# Sheet1.net
KiCad netlist of a schematic drawn in Altium Designer
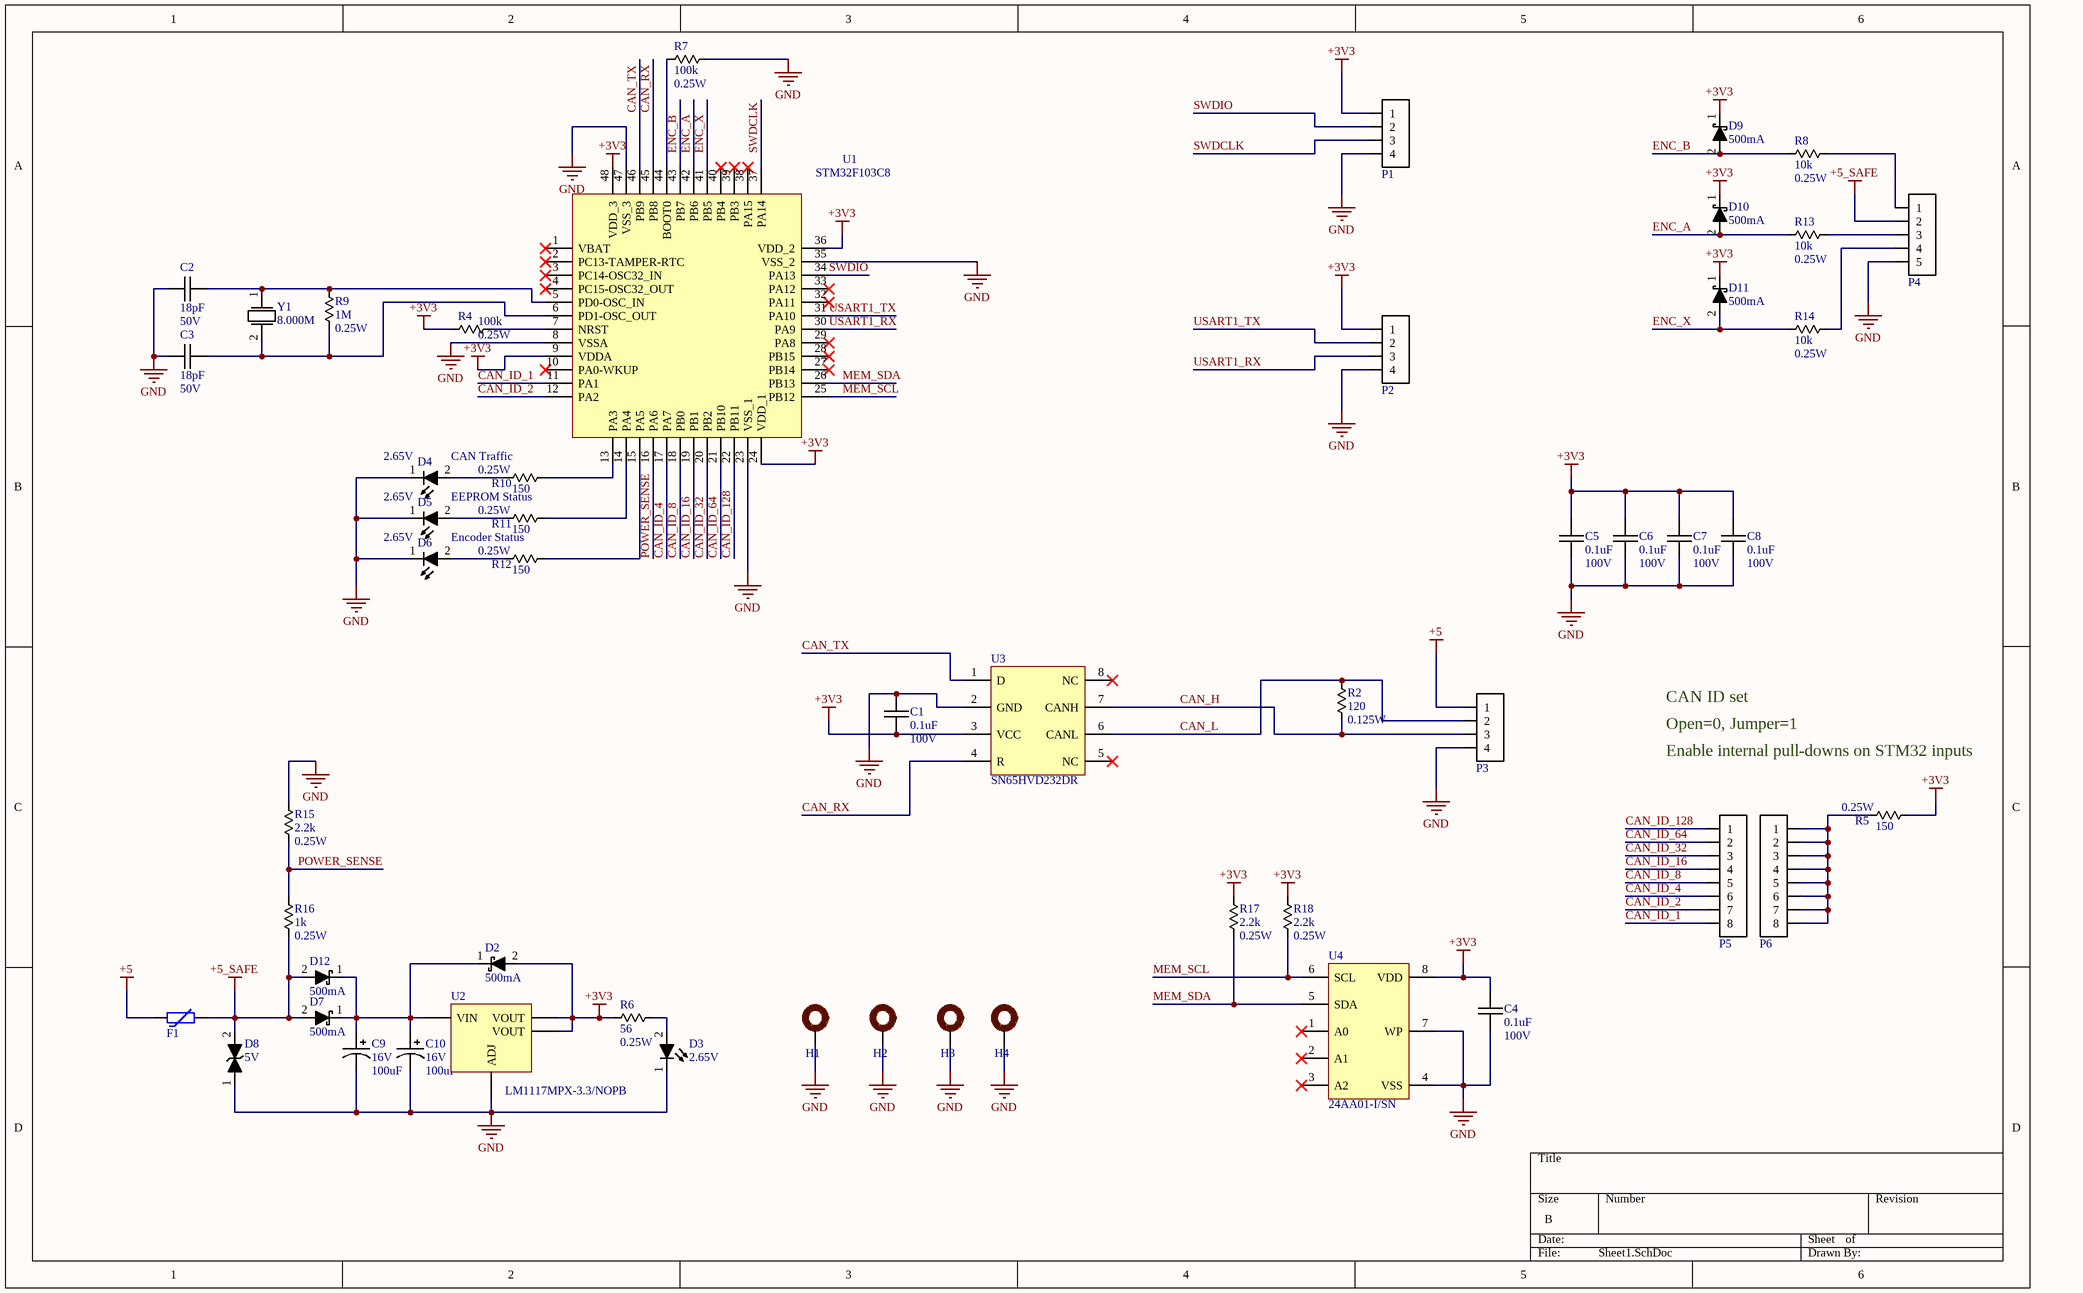
[diagram p0: Sheet1.SchDoc]

(export (version "E")
  (design (tool "Eeschema 10.0.6"))
  (components
    (comp (ref "C1")
      (value "cap_single_np")
      (footprint "chip_0603")
      (description "CAP, 0.1uF, ±10%, 100V, X7R, 0603")
      (fields
        (field (name "TOLERANCE") "±10%")
        (field (name "CAPACITANCE") "0.1uF")
        (field (name "VOLTAGE RATING") "100V")
        (field (name "PART NUMBER") "CAP-00477")
      )
      (libsource (lib "Capacitors") (part "cap_single_np"))
    )
    (comp (ref "C2")
      (value "cap_single_np")
      (footprint "chip_0603")
      (description "CAP, 18pF, ±2%, 50V, C0G, 0603")
      (fields
        (field (name "TOLERANCE") "±2%")
        (field (name "CAPACITANCE") "18pF")
        (field (name "VOLTAGE RATING") "50V")
        (field (name "PART NUMBER") "CAP-00409")
      )
      (libsource (lib "Capacitors") (part "cap_single_np"))
    )
    (comp (ref "C3")
      (value "cap_single_np")
      (footprint "chip_0603")
      (description "CAP, 18pF, ±2%, 50V, C0G, 0603")
      (fields
        (field (name "TOLERANCE") "±2%")
        (field (name "CAPACITANCE") "18pF")
        (field (name "VOLTAGE RATING") "50V")
        (field (name "PART NUMBER") "CAP-00409")
      )
      (libsource (lib "Capacitors") (part "cap_single_np"))
    )
    (comp (ref "C4")
      (value "cap_single_np")
      (footprint "chip_0603")
      (description "CAP, 0.1uF, ±10%, 100V, X7R, 0603")
      (fields
        (field (name "TOLERANCE") "±10%")
        (field (name "CAPACITANCE") "0.1uF")
        (field (name "VOLTAGE RATING") "100V")
        (field (name "PART NUMBER") "CAP-00477")
      )
      (libsource (lib "Capacitors") (part "cap_single_np"))
    )
    (comp (ref "C5")
      (value "cap_single_np")
      (footprint "chip_0603")
      (description "CAP, 0.1uF, ±10%, 100V, X7R, 0603")
      (fields
        (field (name "TOLERANCE") "±10%")
        (field (name "CAPACITANCE") "0.1uF")
        (field (name "VOLTAGE RATING") "100V")
        (field (name "PART NUMBER") "CAP-00530")
      )
      (libsource (lib "Capacitors") (part "cap_single_np"))
    )
    (comp (ref "C6")
      (value "cap_single_np")
      (footprint "chip_0603")
      (description "CAP, 0.1uF, ±10%, 100V, X7R, 0603")
      (fields
        (field (name "TOLERANCE") "±10%")
        (field (name "CAPACITANCE") "0.1uF")
        (field (name "VOLTAGE RATING") "100V")
        (field (name "PART NUMBER") "CAP-00530")
      )
      (libsource (lib "Capacitors") (part "cap_single_np"))
    )
    (comp (ref "C7")
      (value "cap_single_np")
      (footprint "chip_0603")
      (description "CAP, 0.1uF, ±10%, 100V, X7R, 0603")
      (fields
        (field (name "TOLERANCE") "±10%")
        (field (name "CAPACITANCE") "0.1uF")
        (field (name "VOLTAGE RATING") "100V")
        (field (name "PART NUMBER") "CAP-00530")
      )
      (libsource (lib "Capacitors") (part "cap_single_np"))
    )
    (comp (ref "C8")
      (value "cap_single_np")
      (footprint "chip_0603")
      (description "CAP, 0.1uF, ±10%, 100V, X7R, 0603")
      (fields
        (field (name "TOLERANCE") "±10%")
        (field (name "CAPACITANCE") "0.1uF")
        (field (name "VOLTAGE RATING") "100V")
        (field (name "PART NUMBER") "CAP-00530")
      )
      (libsource (lib "Capacitors") (part "cap_single_np"))
    )
    (comp (ref "C9")
      (value "cap_single_p")
      (footprint "chip_2917_AVX_TAJD")
      (description "CAP, 100uF, ±10%, 16V, Tantalum, 2917")
      (fields
        (field (name "TOLERANCE") "±10%")
        (field (name "VOLTAGE RATING") "16V")
        (field (name "CAPACITANCE") "100uF")
        (field (name "PART NUMBER") "CAP-00550")
      )
      (libsource (lib "Capacitors") (part "cap_single_p"))
    )
    (comp (ref "C10")
      (value "cap_single_p")
      (footprint "chip_2917_AVX_TAJD")
      (description "CAP, 100uF, ±10%, 16V, Tantalum, 2917")
      (fields
        (field (name "TOLERANCE") "±10%")
        (field (name "VOLTAGE RATING") "16V")
        (field (name "CAPACITANCE") "100uF")
        (field (name "PART NUMBER") "CAP-00550")
      )
      (libsource (lib "Capacitors") (part "cap_single_p"))
    )
    (comp (ref "D2")
      (value "diode_2")
      (footprint "sod323_0")
      (description "Dio Shtky, 500mA, 0.62V, 30V, SOD-323")
      (fields
        (field (name "CURRENT RATING") "500mA")
        (field (name "PART NUMBER") "DIO-00000")
        (field (name "MANUFACTURER") "ON Semi")
      )
      (libsource (lib "Diodes") (part "diode_2"))
    )
    (comp (ref "D3")
      (value "diode_4")
      (footprint "chip_0603")
      (description "LED, Green, 0603, Low current, HELI2 Series")
      (fields
        (field (name "FORWARD VOLTAGE") "2.65V")
        (field (name "PART NUMBER") "DIO-00050")
        (field (name "MANUFACTURER") "Kingbright")
      )
      (libsource (lib "Diodes") (part "diode_4"))
    )
    (comp (ref "D4")
      (value "diode_4")
      (footprint "chip_0603")
      (description "LED, Blue, 0603, Low current, HELI2 Series")
      (fields
        (field (name "FORWARD VOLTAGE") "2.65V")
        (field (name "PART NUMBER") "DIO-00049")
        (field (name "MANUFACTURER") "Kingbright")
      )
      (libsource (lib "Diodes") (part "diode_4"))
    )
    (comp (ref "D5")
      (value "diode_4")
      (footprint "chip_0603")
      (description "LED, Blue, 0603, Low current, HELI2 Series")
      (fields
        (field (name "FORWARD VOLTAGE") "2.65V")
        (field (name "PART NUMBER") "DIO-00049")
        (field (name "MANUFACTURER") "Kingbright")
      )
      (libsource (lib "Diodes") (part "diode_4"))
    )
    (comp (ref "D6")
      (value "diode_4")
      (footprint "chip_0603")
      (description "LED, Blue, 0603, Low current, HELI2 Series")
      (fields
        (field (name "FORWARD VOLTAGE") "2.65V")
        (field (name "PART NUMBER") "DIO-00049")
        (field (name "MANUFACTURER") "Kingbright")
      )
      (libsource (lib "Diodes") (part "diode_4"))
    )
    (comp (ref "D7")
      (value "diode_2")
      (footprint "sod323_0")
      (description "Dio Shtky, 500mA, 0.62V, 30V, SOD-323")
      (fields
        (field (name "CURRENT RATING") "500mA")
        (field (name "PART NUMBER") "DIO-00000")
        (field (name "MANUFACTURER") "ON Semi")
      )
      (libsource (lib "Diodes") (part "diode_2"))
    )
    (comp (ref "D8")
      (value "diode_5")
      (footprint "sod323_0")
      (description "TVS, 5V, 500W")
      (fields
        (field (name "REVERSE BREAKDOWN VOLTAGE") "5V")
        (field (name "PART NUMBER") "DIO-00037")
        (field (name "MANUFACTURER") "ST")
      )
      (libsource (lib "Diodes") (part "diode_5"))
    )
    (comp (ref "D9")
      (value "diode_2")
      (footprint "sod323_0")
      (description "Dio Shtky, 500mA, 0.62V, 30V, SOD-323")
      (fields
        (field (name "CURRENT RATING") "500mA")
        (field (name "PART NUMBER") "DIO-00000")
        (field (name "MANUFACTURER") "ON Semi")
      )
      (libsource (lib "Diodes") (part "diode_2"))
    )
    (comp (ref "D10")
      (value "diode_2")
      (footprint "sod323_0")
      (description "Dio Shtky, 500mA, 0.62V, 30V, SOD-323")
      (fields
        (field (name "CURRENT RATING") "500mA")
        (field (name "PART NUMBER") "DIO-00000")
        (field (name "MANUFACTURER") "ON Semi")
      )
      (libsource (lib "Diodes") (part "diode_2"))
    )
    (comp (ref "D11")
      (value "diode_2")
      (footprint "sod323_0")
      (description "Dio Shtky, 500mA, 0.62V, 30V, SOD-323")
      (fields
        (field (name "CURRENT RATING") "500mA")
        (field (name "PART NUMBER") "DIO-00000")
        (field (name "MANUFACTURER") "ON Semi")
      )
      (libsource (lib "Diodes") (part "diode_2"))
    )
    (comp (ref "D12")
      (value "diode_2")
      (footprint "sod323_0")
      (description "Dio Shtky, 500mA, 0.62V, 30V, SOD-323")
      (fields
        (field (name "CURRENT RATING") "500mA")
        (field (name "PART NUMBER") "DIO-00000")
        (field (name "MANUFACTURER") "ON Semi")
      )
      (libsource (lib "Diodes") (part "diode_2"))
    )
    (comp (ref "F1")
      (value "PTC_0")
      (footprint "chip_1206")
      (description "PTC Resettable fuse, 6V, 500mA, 1206")
      (fields (field (name "PART NUMBER") "MISC-00008") (field (name "MANUFACTURER") "Eaton"))
      (libsource (lib "Misc") (part "PTC_0"))
    )
    (comp (ref "H1")
      (value "mounting_hole_0")
      (footprint "#8-32_SOCKET_HEAD")
      (description "#8-32 Mounting Hole for Socket Head Cap Screw")
      (fields (field (name "PART NUMBER") "MISC-00027"))
      (libsource (lib "Misc") (part "mounting_hole_0"))
    )
    (comp (ref "H2")
      (value "mounting_hole_0")
      (footprint "#8-32_SOCKET_HEAD")
      (description "#8-32 Mounting Hole for Socket Head Cap Screw")
      (fields (field (name "PART NUMBER") "MISC-00027"))
      (libsource (lib "Misc") (part "mounting_hole_0"))
    )
    (comp (ref "H3")
      (value "mounting_hole_0")
      (footprint "#8-32_SOCKET_HEAD")
      (description "#8-32 Mounting Hole for Socket Head Cap Screw")
      (fields (field (name "PART NUMBER") "MISC-00027"))
      (libsource (lib "Misc") (part "mounting_hole_0"))
    )
    (comp (ref "H4")
      (value "mounting_hole_0")
      (footprint "#8-32_SOCKET_HEAD")
      (description "#8-32 Mounting Hole for Socket Head Cap Screw")
      (fields (field (name "PART NUMBER") "MISC-00027"))
      (libsource (lib "Misc") (part "mounting_hole_0"))
    )
    (comp (ref "P1")
      (value "conn-4x1_0")
      (footprint "HDDR_4x1_0")
      (description "Header 4x1, 0.1\"")
      (fields (field (name "PART NUMBER") "CONN-00029"))
      (libsource (lib "Connectors") (part "conn-4x1_0"))
    )
    (comp (ref "P2")
      (value "conn-4x1_0")
      (footprint "HDDR_4x1_0")
      (description "Header 4x1, 0.1\"")
      (fields (field (name "PART NUMBER") "CONN-00029"))
      (libsource (lib "Connectors") (part "conn-4x1_0"))
    )
    (comp (ref "P3")
      (value "conn-4x1_0")
      (footprint "TERM_3.50MM_4x1_0")
      (description "Term Blk, 4 Pos, 16A, 3.5mm Pitch")
      (fields (field (name "PART NUMBER") "CONN-00024") (field (name "MANUFACTURER") "Phoenix Contact"))
      (libsource (lib "Connectors") (part "conn-4x1_0"))
    )
    (comp (ref "P4")
      (value "conn-5x1_0")
      (footprint "JST_PHR_5_0")
      (description "JST PHR 5x1")
      (fields (field (name "PART NUMBER") "CONN-00016") (field (name "MANUFACTURER") "JST"))
      (libsource (lib "Connectors") (part "conn-5x1_0"))
    )
    (comp (ref "P5")
      (value "conn-8x1_0")
      (footprint "hddr_8x1_0")
      (description "Header 8x1, 0.1\"")
      (fields (field (name "PART NUMBER") "CONN-00003"))
      (libsource (lib "Connectors") (part "conn-8x1_0"))
    )
    (comp (ref "P6")
      (value "conn-8x1_0")
      (footprint "hddr_8x1_0")
      (description "Header 8x1, 0.1\"")
      (fields (field (name "PART NUMBER") "CONN-00003"))
      (libsource (lib "Connectors") (part "conn-8x1_0"))
    )
    (comp (ref "R2")
      (value "res_single")
      (footprint "chip_0805")
      (description "RES SMD 120 OHM 1% 1/8W 0805")
      (fields
        (field (name "TOLERANCE") "1%")
        (field (name "RESISTANCE") "120")
        (field (name "POWER RATING") "0.125W")
        (field (name "PART NUMBER") "RES-00183")
      )
      (libsource (lib "Resistors") (part "res_single"))
    )
    (comp (ref "R4")
      (value "res_single")
      (footprint "chip_0603")
      (description "RES SMD 100K OHM 1% 1/4W 0603")
      (fields
        (field (name "TOLERANCE") "1%")
        (field (name "RESISTANCE") "100k")
        (field (name "POWER RATING") "0.25W")
        (field (name "PART NUMBER") "RES-00301")
      )
      (libsource (lib "Resistors") (part "res_single"))
    )
    (comp (ref "R5")
      (value "res_single")
      (footprint "chip_0603")
      (description "RES SMD 150 OHM 1% 1/4W 0603")
      (fields
        (field (name "TOLERANCE") "1%")
        (field (name "RESISTANCE") "150")
        (field (name "POWER RATING") "0.25W")
        (field (name "PART NUMBER") "RES-00188")
      )
      (libsource (lib "Resistors") (part "res_single"))
    )
    (comp (ref "R6")
      (value "res_single")
      (footprint "chip_0603")
      (description "RES SMD 56 OHM 1% 1/4W 0603")
      (fields
        (field (name "TOLERANCE") "1%")
        (field (name "RESISTANCE") "56")
        (field (name "POWER RATING") "0.25W")
        (field (name "PART NUMBER") "RES-00159")
      )
      (libsource (lib "Resistors") (part "res_single"))
    )
    (comp (ref "R7")
      (value "res_single")
      (footprint "chip_0603")
      (description "RES SMD 100K OHM 1% 1/4W 0603")
      (fields
        (field (name "TOLERANCE") "1%")
        (field (name "RESISTANCE") "100k")
        (field (name "POWER RATING") "0.25W")
        (field (name "PART NUMBER") "RES-00301")
      )
      (libsource (lib "Resistors") (part "res_single"))
    )
    (comp (ref "R8")
      (value "res_single")
      (footprint "chip_0603")
      (description "RES SMD 10K OHM 1% 1/4W 0603")
      (fields
        (field (name "TOLERANCE") "1%")
        (field (name "RESISTANCE") "10k")
        (field (name "POWER RATING") "0.25W")
        (field (name "PART NUMBER") "RES-00306")
      )
      (libsource (lib "Resistors") (part "res_single"))
    )
    (comp (ref "R9")
      (value "res_single")
      (footprint "chip_0603")
      (description "RES SMD 1M OHM 1% 1/4W 0603")
      (fields
        (field (name "TOLERANCE") "1%")
        (field (name "RESISTANCE") "1M")
        (field (name "POWER RATING") "0.25W")
        (field (name "PART NUMBER") "RES-00362")
      )
      (libsource (lib "Resistors") (part "res_single"))
    )
    (comp (ref "R10")
      (value "res_single")
      (footprint "chip_0603")
      (description "RES SMD 150 OHM 1% 1/4W 0603")
      (fields
        (field (name "TOLERANCE") "1%")
        (field (name "RESISTANCE") "150")
        (field (name "POWER RATING") "0.25W")
        (field (name "PART NUMBER") "RES-00188")
      )
      (libsource (lib "Resistors") (part "res_single"))
    )
    (comp (ref "R11")
      (value "res_single")
      (footprint "chip_0603")
      (description "RES SMD 150 OHM 1% 1/4W 0603")
      (fields
        (field (name "TOLERANCE") "1%")
        (field (name "RESISTANCE") "150")
        (field (name "POWER RATING") "0.25W")
        (field (name "PART NUMBER") "RES-00188")
      )
      (libsource (lib "Resistors") (part "res_single"))
    )
    (comp (ref "R12")
      (value "res_single")
      (footprint "chip_0603")
      (description "RES SMD 150 OHM 1% 1/4W 0603")
      (fields
        (field (name "TOLERANCE") "1%")
        (field (name "RESISTANCE") "150")
        (field (name "POWER RATING") "0.25W")
        (field (name "PART NUMBER") "RES-00188")
      )
      (libsource (lib "Resistors") (part "res_single"))
    )
    (comp (ref "R13")
      (value "res_single")
      (footprint "chip_0603")
      (description "RES SMD 10K OHM 1% 1/4W 0603")
      (fields
        (field (name "TOLERANCE") "1%")
        (field (name "RESISTANCE") "10k")
        (field (name "POWER RATING") "0.25W")
        (field (name "PART NUMBER") "RES-00306")
      )
      (libsource (lib "Resistors") (part "res_single"))
    )
    (comp (ref "R14")
      (value "res_single")
      (footprint "chip_0603")
      (description "RES SMD 10K OHM 1% 1/4W 0603")
      (fields
        (field (name "TOLERANCE") "1%")
        (field (name "RESISTANCE") "10k")
        (field (name "POWER RATING") "0.25W")
        (field (name "PART NUMBER") "RES-00306")
      )
      (libsource (lib "Resistors") (part "res_single"))
    )
    (comp (ref "R15")
      (value "res_single")
      (footprint "chip_0603")
      (description "RES SMD 2.2K OHM 1% 1/4W 0603")
      (fields
        (field (name "TOLERANCE") "1%")
        (field (name "RESISTANCE") "2.2k")
        (field (name "POWER RATING") "0.25W")
        (field (name "PART NUMBER") "RES-00365")
      )
      (libsource (lib "Resistors") (part "res_single"))
    )
    (comp (ref "R16")
      (value "res_single")
      (footprint "chip_0603")
      (description "RES SMD 1K OHM 1% 1/4W 0603")
      (fields
        (field (name "TOLERANCE") "1%")
        (field (name "RESISTANCE") "1k")
        (field (name "POWER RATING") "0.25W")
        (field (name "PART NUMBER") "RES-00360")
      )
      (libsource (lib "Resistors") (part "res_single"))
    )
    (comp (ref "R17")
      (value "res_single")
      (footprint "chip_0603")
      (description "RES SMD 2.2K OHM 1% 1/4W 0603")
      (fields
        (field (name "TOLERANCE") "1%")
        (field (name "RESISTANCE") "2.2k")
        (field (name "POWER RATING") "0.25W")
        (field (name "PART NUMBER") "RES-00365")
      )
      (libsource (lib "Resistors") (part "res_single"))
    )
    (comp (ref "R18")
      (value "res_single")
      (footprint "chip_0603")
      (description "RES SMD 2.2K OHM 1% 1/4W 0603")
      (fields
        (field (name "TOLERANCE") "1%")
        (field (name "RESISTANCE") "2.2k")
        (field (name "POWER RATING") "0.25W")
        (field (name "PART NUMBER") "RES-00365")
      )
      (libsource (lib "Resistors") (part "res_single"))
    )
    (comp (ref "U1")
      (value "STM32F103C8")
      (footprint "LQFP48_0")
      (description "STM32 M3, LQFP-48")
      (fields
        (field (name "MANUFACTURER PN") "STM32F103C8")
        (field (name "PART NUMBER") "UCTRL-00008")
        (field (name "MANUFACTURER") "ST")
      )
      (libsource (lib "Microcontrollers") (part "STM32F103C8"))
    )
    (comp (ref "U2")
      (value "LM1117")
      (footprint "sot-223-4")
      (description "REG, Linear, Fixed 3V3, 800mA, SOT-223")
      (fields
        (field (name "MANUFACTURER PN") "LM1117MPX-3.3/NOPB")
        (field (name "PART NUMBER") "PWREG-00018")
        (field (name "MANUFACTURER") "TI")
      )
      (libsource (lib "Power Reg") (part "LM1117"))
    )
    (comp (ref "U3")
      (value "SN65HVD232")
      (footprint "SO-8")
      (description "CANbus Transceiver, Single channel, SN65HVD232")
      (fields
        (field (name "MANUFACTURER PN") "SN65HVD232DR")
        (field (name "PART NUMBER") "IFACE-00008")
        (field (name "MANUFACTURER") "TI")
      )
      (libsource (lib "Interfaces") (part "SN65HVD232"))
    )
    (comp (ref "U4")
      (value "24AA01")
      (footprint "SO-8")
      (description "EEPROM, 1K-bit, I2C, 400kHz, 24AA01, 8-SOIC")
      (fields
        (field (name "MANUFACTURER PN") "24AA01-I/SN")
        (field (name "PART NUMBER") "LOGIC-00028")
        (field (name "MANUFACTURER") "Microchip")
      )
      (libsource (lib "Logic") (part "24AA01"))
    )
    (comp (ref "Y1")
      (value "osc_xtal_2p_0")
      (footprint "ABLS_AT49_OSC")
      (description "XTAL, 8MHz, 18pF, 20ppm")
      (fields
        (field (name "TOLERANCE") "20ppm")
        (field (name "FREQUENCY") "8.000M")
        (field (name "PART NUMBER") "OSC-00002")
      )
      (libsource (lib "Oscillators") (part "osc_xtal_2p_0"))
    )
  )
  (nets
    (net (code "1") (name "+3V3") (class "Default")
      (node (ref "C1") (pin "2") (pinfunction "2_2") (pintype "passive"))
      (node (ref "C4") (pin "1") (pinfunction "1_1") (pintype "passive"))
      (node (ref "C5") (pin "2") (pinfunction "2_2") (pintype "passive"))
      (node (ref "C6") (pin "2") (pinfunction "2_2") (pintype "passive"))
      (node (ref "C7") (pin "2") (pinfunction "2_2") (pintype "passive"))
      (node (ref "C8") (pin "2") (pinfunction "2_2") (pintype "passive"))
      (node (ref "D10") (pin "1") (pinfunction "1_1") (pintype "passive"))
      (node (ref "D11") (pin "1") (pinfunction "1_1") (pintype "passive"))
      (node (ref "D2") (pin "2") (pinfunction "2_2") (pintype "passive"))
      (node (ref "D9") (pin "1") (pinfunction "1_1") (pintype "passive"))
      (node (ref "P1") (pin "1") (pinfunction "1_1") (pintype "passive"))
      (node (ref "P2") (pin "1") (pinfunction "1_1") (pintype "passive"))
      (node (ref "R17") (pin "1") (pinfunction "1_1") (pintype "passive"))
      (node (ref "R18") (pin "1") (pinfunction "1_1") (pintype "passive"))
      (node (ref "R4") (pin "2") (pinfunction "2_2") (pintype "passive"))
      (node (ref "R5") (pin "2") (pinfunction "2_2") (pintype "passive"))
      (node (ref "R6") (pin "1") (pinfunction "1_1") (pintype "passive"))
      (node (ref "U1") (pin "24") (pinfunction "VDD_1_24") (pintype "passive"))
      (node (ref "U1") (pin "36") (pinfunction "VDD_2_36") (pintype "passive"))
      (node (ref "U1") (pin "48") (pinfunction "VDD_3_48") (pintype "passive"))
      (node (ref "U1") (pin "9") (pinfunction "VDDA_9") (pintype "passive"))
      (node (ref "U2") (pin "2") (pinfunction "VOUT_2") (pintype "passive"))
      (node (ref "U2") (pin "4") (pinfunction "VOUT_4") (pintype "passive"))
      (node (ref "U3") (pin "3") (pinfunction "VCC_3") (pintype "passive"))
      (node (ref "U4") (pin "8") (pinfunction "VDD_8") (pintype "passive"))
    )
    (net (code "2") (name "+5") (class "Default")
      (node (ref "F1") (pin "1") (pinfunction "1_1") (pintype "passive"))
      (node (ref "P3") (pin "1") (pinfunction "1_1") (pintype "passive"))
    )
    (net (code "3") (name "+5_SAFE") (class "Default")
      (node (ref "D12") (pin "2") (pinfunction "2_2") (pintype "passive"))
      (node (ref "D7") (pin "2") (pinfunction "2_2") (pintype "passive"))
      (node (ref "D8") (pin "2") (pinfunction "2_2") (pintype "passive"))
      (node (ref "F1") (pin "2") (pinfunction "2_2") (pintype "passive"))
      (node (ref "P4") (pin "2") (pinfunction "2_2") (pintype "passive"))
      (node (ref "R16") (pin "2") (pinfunction "2_2") (pintype "passive"))
    )
    (net (code "4") (name "/CAN_H") (class "Default")
      (node (ref "P3") (pin "3") (pinfunction "3_3") (pintype "passive"))
      (node (ref "R2") (pin "2") (pinfunction "2_2") (pintype "passive"))
      (node (ref "U3") (pin "7") (pinfunction "CANH_7") (pintype "passive"))
    )
    (net (code "5") (name "/CAN_ID_1") (class "Default")
      (node (ref "P5") (pin "8") (pinfunction "8_8") (pintype "passive"))
      (node (ref "U1") (pin "11") (pinfunction "PA1_11") (pintype "passive"))
    )
    (net (code "6") (name "/CAN_ID_2") (class "Default")
      (node (ref "P5") (pin "7") (pinfunction "7_7") (pintype "passive"))
      (node (ref "U1") (pin "12") (pinfunction "PA2_12") (pintype "passive"))
    )
    (net (code "7") (name "/CAN_ID_4") (class "Default")
      (node (ref "P5") (pin "6") (pinfunction "6_6") (pintype "passive"))
      (node (ref "U1") (pin "17") (pinfunction "PA7_17") (pintype "passive"))
    )
    (net (code "8") (name "/CAN_ID_8") (class "Default")
      (node (ref "P5") (pin "5") (pinfunction "5_5") (pintype "passive"))
      (node (ref "U1") (pin "18") (pinfunction "PB0_18") (pintype "passive"))
    )
    (net (code "9") (name "/CAN_ID_16") (class "Default")
      (node (ref "P5") (pin "4") (pinfunction "4_4") (pintype "passive"))
      (node (ref "U1") (pin "19") (pinfunction "PB1_19") (pintype "passive"))
    )
    (net (code "10") (name "/CAN_ID_32") (class "Default")
      (node (ref "P5") (pin "3") (pinfunction "3_3") (pintype "passive"))
      (node (ref "U1") (pin "20") (pinfunction "PB2_20") (pintype "passive"))
    )
    (net (code "11") (name "/CAN_ID_64") (class "Default")
      (node (ref "P5") (pin "2") (pinfunction "2_2") (pintype "passive"))
      (node (ref "U1") (pin "21") (pinfunction "PB10_21") (pintype "passive"))
    )
    (net (code "12") (name "/CAN_ID_128") (class "Default")
      (node (ref "P5") (pin "1") (pinfunction "1_1") (pintype "passive"))
      (node (ref "U1") (pin "22") (pinfunction "PB11_22") (pintype "passive"))
    )
    (net (code "13") (name "/CAN_L") (class "Default")
      (node (ref "P3") (pin "2") (pinfunction "2_2") (pintype "passive"))
      (node (ref "R2") (pin "1") (pinfunction "1_1") (pintype "passive"))
      (node (ref "U3") (pin "6") (pinfunction "CANL_6") (pintype "passive"))
    )
    (net (code "14") (name "/CAN_RX") (class "Default")
      (node (ref "U1") (pin "45") (pinfunction "PB8_45") (pintype "passive"))
      (node (ref "U3") (pin "4") (pinfunction "R_4") (pintype "passive"))
    )
    (net (code "15") (name "/CAN_TX") (class "Default")
      (node (ref "U1") (pin "46") (pinfunction "PB9_46") (pintype "passive"))
      (node (ref "U3") (pin "1") (pinfunction "D_1") (pintype "passive"))
    )
    (net (code "16") (name "/ENC_A") (class "Default")
      (node (ref "D10") (pin "2") (pinfunction "2_2") (pintype "passive"))
      (node (ref "R13") (pin "1") (pinfunction "1_1") (pintype "passive"))
      (node (ref "U1") (pin "42") (pinfunction "PB6_42") (pintype "passive"))
    )
    (net (code "17") (name "/ENC_B") (class "Default")
      (node (ref "D9") (pin "2") (pinfunction "2_2") (pintype "passive"))
      (node (ref "R8") (pin "1") (pinfunction "1_1") (pintype "passive"))
      (node (ref "U1") (pin "43") (pinfunction "PB7_43") (pintype "passive"))
    )
    (net (code "18") (name "/ENC_X") (class "Default")
      (node (ref "D11") (pin "2") (pinfunction "2_2") (pintype "passive"))
      (node (ref "R14") (pin "1") (pinfunction "1_1") (pintype "passive"))
      (node (ref "U1") (pin "41") (pinfunction "PB5_41") (pintype "passive"))
    )
    (net (code "19") (name "/MEM_SCL") (class "Default")
      (node (ref "R18") (pin "2") (pinfunction "2_2") (pintype "passive"))
      (node (ref "U1") (pin "25") (pinfunction "PB12_25") (pintype "passive"))
      (node (ref "U4") (pin "6") (pinfunction "SCL_6") (pintype "passive"))
    )
    (net (code "20") (name "/MEM_SDA") (class "Default")
      (node (ref "R17") (pin "2") (pinfunction "2_2") (pintype "passive"))
      (node (ref "U1") (pin "26") (pinfunction "PB13_26") (pintype "passive"))
      (node (ref "U4") (pin "5") (pinfunction "SDA_5") (pintype "passive"))
    )
    (net (code "21") (name "/POWER_SENSE") (class "Default")
      (node (ref "R15") (pin "2") (pinfunction "2_2") (pintype "passive"))
      (node (ref "R16") (pin "1") (pinfunction "1_1") (pintype "passive"))
      (node (ref "U1") (pin "16") (pinfunction "PA6_16") (pintype "passive"))
    )
    (net (code "22") (name "/SWDCLK") (class "Default")
      (node (ref "P1") (pin "3") (pinfunction "3_3") (pintype "passive"))
      (node (ref "U1") (pin "37") (pinfunction "PA14_37") (pintype "passive"))
    )
    (net (code "23") (name "/SWDIO") (class "Default")
      (node (ref "P1") (pin "2") (pinfunction "2_2") (pintype "passive"))
      (node (ref "U1") (pin "34") (pinfunction "PA13_34") (pintype "passive"))
    )
    (net (code "24") (name "/USART1_RX") (class "Default")
      (node (ref "P2") (pin "3") (pinfunction "3_3") (pintype "passive"))
      (node (ref "U1") (pin "30") (pinfunction "PA9_30") (pintype "passive"))
    )
    (net (code "25") (name "/USART1_TX") (class "Default")
      (node (ref "P2") (pin "2") (pinfunction "2_2") (pintype "passive"))
      (node (ref "U1") (pin "31") (pinfunction "PA10_31") (pintype "passive"))
    )
    (net (code "26") (name "GND") (class "Default")
      (node (ref "C1") (pin "1") (pinfunction "1_1") (pintype "passive"))
      (node (ref "C10") (pin "2") (pinfunction "2_2") (pintype "passive"))
      (node (ref "C2") (pin "2") (pinfunction "2_2") (pintype "passive"))
      (node (ref "C3") (pin "2") (pinfunction "2_2") (pintype "passive"))
      (node (ref "C4") (pin "2") (pinfunction "2_2") (pintype "passive"))
      (node (ref "C5") (pin "1") (pinfunction "1_1") (pintype "passive"))
      (node (ref "C6") (pin "1") (pinfunction "1_1") (pintype "passive"))
      (node (ref "C7") (pin "1") (pinfunction "1_1") (pintype "passive"))
      (node (ref "C8") (pin "1") (pinfunction "1_1") (pintype "passive"))
      (node (ref "C9") (pin "2") (pinfunction "2_2") (pintype "passive"))
      (node (ref "D3") (pin "1") (pinfunction "1_1") (pintype "passive"))
      (node (ref "D4") (pin "1") (pinfunction "1_1") (pintype "passive"))
      (node (ref "D5") (pin "1") (pinfunction "1_1") (pintype "passive"))
      (node (ref "D6") (pin "1") (pinfunction "1_1") (pintype "passive"))
      (node (ref "D8") (pin "1") (pinfunction "1_1") (pintype "passive"))
      (node (ref "H1") (pin "0") (pinfunction "A_0") (pintype "passive"))
      (node (ref "H2") (pin "0") (pinfunction "A_0") (pintype "passive"))
      (node (ref "H3") (pin "0") (pinfunction "A_0") (pintype "passive"))
      (node (ref "H4") (pin "0") (pinfunction "A_0") (pintype "passive"))
      (node (ref "P1") (pin "4") (pinfunction "4_4") (pintype "passive"))
      (node (ref "P2") (pin "4") (pinfunction "4_4") (pintype "passive"))
      (node (ref "P3") (pin "4") (pinfunction "4_4") (pintype "passive"))
      (node (ref "P4") (pin "5") (pinfunction "5_5") (pintype "passive"))
      (node (ref "R15") (pin "1") (pinfunction "1_1") (pintype "passive"))
      (node (ref "R7") (pin "1") (pinfunction "1_1") (pintype "passive"))
      (node (ref "U1") (pin "23") (pinfunction "VSS_1_23") (pintype "passive"))
      (node (ref "U1") (pin "35") (pinfunction "VSS_2_35") (pintype "passive"))
      (node (ref "U1") (pin "47") (pinfunction "VSS_3_47") (pintype "passive"))
      (node (ref "U1") (pin "8") (pinfunction "VSSA_8") (pintype "passive"))
      (node (ref "U2") (pin "1") (pinfunction "ADJ_1") (pintype "passive"))
      (node (ref "U3") (pin "2") (pinfunction "GND_2") (pintype "passive"))
      (node (ref "U4") (pin "4") (pinfunction "VSS_4") (pintype "passive"))
      (node (ref "U4") (pin "7") (pinfunction "WP_7") (pintype "passive"))
    )
    (net (code "27") (name "Net-(D3-Pad2)") (class "Default")
      (node (ref "D3") (pin "2") (pinfunction "2_2") (pintype "passive"))
      (node (ref "R6") (pin "2") (pinfunction "2_2") (pintype "passive"))
    )
    (net (code "28") (name "Net-(D4-Pad2)") (class "Default")
      (node (ref "D4") (pin "2") (pinfunction "2_2") (pintype "passive"))
      (node (ref "R10") (pin "1") (pinfunction "1_1") (pintype "passive"))
    )
    (net (code "29") (name "Net-(D5-Pad2)") (class "Default")
      (node (ref "D5") (pin "2") (pinfunction "2_2") (pintype "passive"))
      (node (ref "R11") (pin "1") (pinfunction "1_1") (pintype "passive"))
    )
    (net (code "30") (name "Net-(D6-Pad2)") (class "Default")
      (node (ref "D6") (pin "2") (pinfunction "2_2") (pintype "passive"))
      (node (ref "R12") (pin "1") (pinfunction "1_1") (pintype "passive"))
    )
    (net (code "31") (name "Net-(P4-Pad1)") (class "Default")
      (node (ref "P4") (pin "1") (pinfunction "1_1") (pintype "passive"))
      (node (ref "R8") (pin "2") (pinfunction "2_2") (pintype "passive"))
    )
    (net (code "32") (name "Net-(P4-Pad3)") (class "Default")
      (node (ref "P4") (pin "3") (pinfunction "3_3") (pintype "passive"))
      (node (ref "R13") (pin "2") (pinfunction "2_2") (pintype "passive"))
    )
    (net (code "33") (name "Net-(P4-Pad4)") (class "Default")
      (node (ref "P4") (pin "4") (pinfunction "4_4") (pintype "passive"))
      (node (ref "R14") (pin "2") (pinfunction "2_2") (pintype "passive"))
    )
    (net (code "34") (name "Net-(P6-Pad1)") (class "Default")
      (node (ref "P6") (pin "1") (pinfunction "1_1") (pintype "passive"))
      (node (ref "P6") (pin "2") (pinfunction "2_2") (pintype "passive"))
      (node (ref "P6") (pin "3") (pinfunction "3_3") (pintype "passive"))
      (node (ref "P6") (pin "4") (pinfunction "4_4") (pintype "passive"))
      (node (ref "P6") (pin "5") (pinfunction "5_5") (pintype "passive"))
      (node (ref "P6") (pin "6") (pinfunction "6_6") (pintype "passive"))
      (node (ref "P6") (pin "7") (pinfunction "7_7") (pintype "passive"))
      (node (ref "P6") (pin "8") (pinfunction "8_8") (pintype "passive"))
      (node (ref "R5") (pin "1") (pinfunction "1_1") (pintype "passive"))
    )
    (net (code "35") (name "Net-(U1-BOOT0)") (class "Default")
      (node (ref "R7") (pin "2") (pinfunction "2_2") (pintype "passive"))
      (node (ref "U1") (pin "44") (pinfunction "BOOT0_44") (pintype "passive"))
    )
    (net (code "36") (name "Net-(U1-NRST)") (class "Default")
      (node (ref "R4") (pin "1") (pinfunction "1_1") (pintype "passive"))
      (node (ref "U1") (pin "7") (pinfunction "NRST_7") (pintype "passive"))
    )
    (net (code "37") (name "Net-(U1-PA3)") (class "Default")
      (node (ref "R10") (pin "2") (pinfunction "2_2") (pintype "passive"))
      (node (ref "U1") (pin "13") (pinfunction "PA3_13") (pintype "passive"))
    )
    (net (code "38") (name "Net-(U1-PA4)") (class "Default")
      (node (ref "R11") (pin "2") (pinfunction "2_2") (pintype "passive"))
      (node (ref "U1") (pin "14") (pinfunction "PA4_14") (pintype "passive"))
    )
    (net (code "39") (name "Net-(U1-PA5)") (class "Default")
      (node (ref "R12") (pin "2") (pinfunction "2_2") (pintype "passive"))
      (node (ref "U1") (pin "15") (pinfunction "PA5_15") (pintype "passive"))
    )
    (net (code "40") (name "Net-(U1-PD0-OSC_IN)") (class "Default")
      (node (ref "C2") (pin "1") (pinfunction "1_1") (pintype "passive"))
      (node (ref "R9") (pin "1") (pinfunction "1_1") (pintype "passive"))
      (node (ref "U1") (pin "5") (pinfunction "PD0-OSC_IN_5") (pintype "passive"))
      (node (ref "Y1") (pin "1") (pinfunction "20_1") (pintype "passive"))
    )
    (net (code "41") (name "Net-(U1-PD1-OSC_OUT)") (class "Default")
      (node (ref "C3") (pin "1") (pinfunction "1_1") (pintype "passive"))
      (node (ref "R9") (pin "2") (pinfunction "2_2") (pintype "passive"))
      (node (ref "U1") (pin "6") (pinfunction "PD1-OSC_OUT_6") (pintype "passive"))
      (node (ref "Y1") (pin "2") (pinfunction "20_2") (pintype "passive"))
    )
    (net (code "42") (name "Net-(U2-VIN)") (class "Default")
      (node (ref "C10") (pin "1") (pinfunction "1_1") (pintype "passive"))
      (node (ref "C9") (pin "1") (pinfunction "1_1") (pintype "passive"))
      (node (ref "D12") (pin "1") (pinfunction "1_1") (pintype "passive"))
      (node (ref "D2") (pin "1") (pinfunction "1_1") (pintype "passive"))
      (node (ref "D7") (pin "1") (pinfunction "1_1") (pintype "passive"))
      (node (ref "U2") (pin "3") (pinfunction "VIN_3") (pintype "passive"))
    )
    (net (code "43") (name "unconnected-(U1-PA0-WKUP-Pad10)") (class "Default")
      (node (ref "U1") (pin "10") (pinfunction "PA0-WKUP_10") (pintype "passive+no_connect"))
    )
    (net (code "44") (name "unconnected-(U1-PA8-Pad29)") (class "Default")
      (node (ref "U1") (pin "29") (pinfunction "PA8_29") (pintype "passive+no_connect"))
    )
    (net (code "45") (name "unconnected-(U1-PA11-Pad32)") (class "Default")
      (node (ref "U1") (pin "32") (pinfunction "PA11_32") (pintype "passive+no_connect"))
    )
    (net (code "46") (name "unconnected-(U1-PA12-Pad33)") (class "Default")
      (node (ref "U1") (pin "33") (pinfunction "PA12_33") (pintype "passive+no_connect"))
    )
    (net (code "47") (name "unconnected-(U1-PA15-Pad38)") (class "Default")
      (node (ref "U1") (pin "38") (pinfunction "PA15_38") (pintype "passive+no_connect"))
    )
    (net (code "48") (name "unconnected-(U1-PB3-Pad39)") (class "Default")
      (node (ref "U1") (pin "39") (pinfunction "PB3_39") (pintype "passive+no_connect"))
    )
    (net (code "49") (name "unconnected-(U1-PB4-Pad40)") (class "Default")
      (node (ref "U1") (pin "40") (pinfunction "PB4_40") (pintype "passive+no_connect"))
    )
    (net (code "50") (name "unconnected-(U1-PB14-Pad27)") (class "Default")
      (node (ref "U1") (pin "27") (pinfunction "PB14_27") (pintype "passive+no_connect"))
    )
    (net (code "51") (name "unconnected-(U1-PB15-Pad28)") (class "Default")
      (node (ref "U1") (pin "28") (pinfunction "PB15_28") (pintype "passive+no_connect"))
    )
    (net (code "52") (name "unconnected-(U1-PC13-TAMPER-RTC-Pad2)") (class "Default")
      (node (ref "U1") (pin "2") (pinfunction "PC13-TAMPER-RTC_2") (pintype "passive+no_connect"))
    )
    (net (code "53") (name "unconnected-(U1-PC14-OSC32_IN-Pad3)") (class "Default")
      (node (ref "U1") (pin "3") (pinfunction "PC14-OSC32_IN_3") (pintype "passive+no_connect"))
    )
    (net (code "54") (name "unconnected-(U1-PC15-OSC32_OUT-Pad4)") (class "Default")
      (node (ref "U1") (pin "4") (pinfunction "PC15-OSC32_OUT_4") (pintype "passive+no_connect"))
    )
    (net (code "55") (name "unconnected-(U1-VBAT-Pad1)") (class "Default")
      (node (ref "U1") (pin "1") (pinfunction "VBAT_1") (pintype "passive+no_connect"))
    )
    (net (code "56") (name "unconnected-(U3-NC-Pad5)") (class "Default")
      (node (ref "U3") (pin "5") (pinfunction "NC_5") (pintype "passive+no_connect"))
    )
    (net (code "57") (name "unconnected-(U3-NC-Pad8)") (class "Default")
      (node (ref "U3") (pin "8") (pinfunction "NC_8") (pintype "passive+no_connect"))
    )
    (net (code "58") (name "unconnected-(U4-A0-Pad1)") (class "Default")
      (node (ref "U4") (pin "1") (pinfunction "A0_1") (pintype "passive+no_connect"))
    )
    (net (code "59") (name "unconnected-(U4-A1-Pad2)") (class "Default")
      (node (ref "U4") (pin "2") (pinfunction "A1_2") (pintype "passive+no_connect"))
    )
    (net (code "60") (name "unconnected-(U4-A2-Pad3)") (class "Default")
      (node (ref "U4") (pin "3") (pinfunction "A2_3") (pintype "passive+no_connect"))
    )
  )
)
